# mod_B.net
KiCad netlist of a schematic drawn in EAGLE
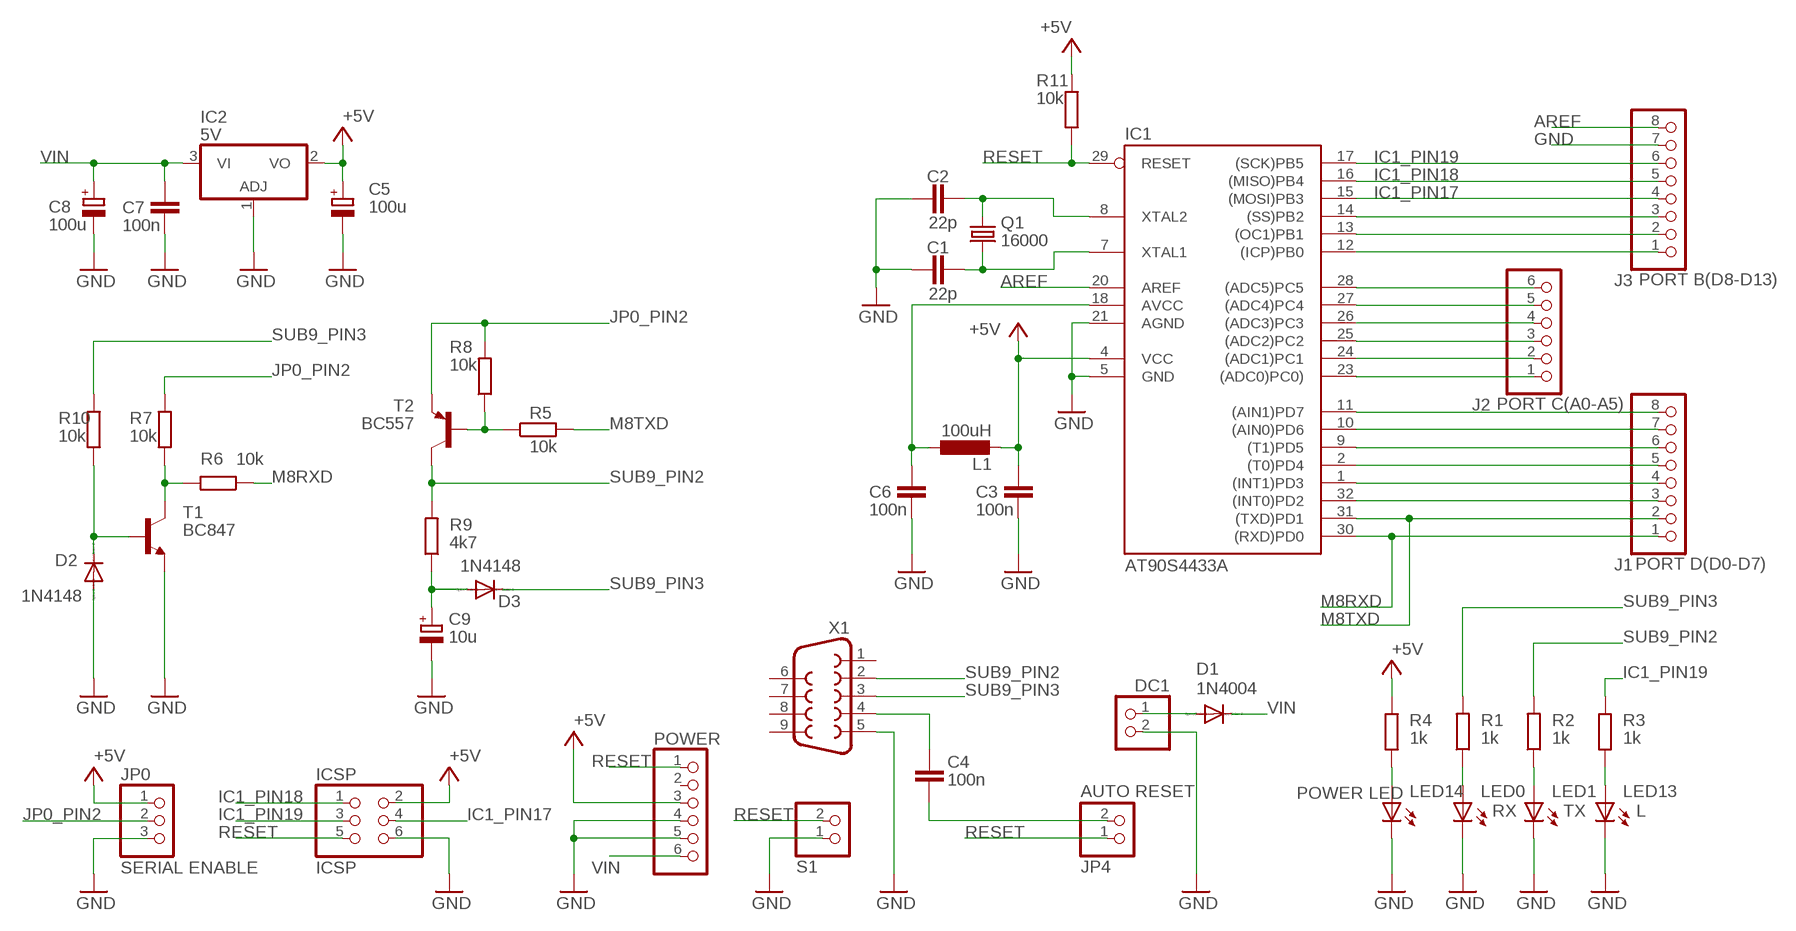
[diagram p0: schematic, sheet 1]

(export (version "E")
  (design (tool "Eeschema 10.0.6"))
  (components
    (comp (ref "C1")
      (value "22p")
      (footprint "eagle-import:C0805")
      (libsource (lib "eagle-import") (part "C-EUC0805"))
    )
    (comp (ref "C2")
      (value "22p")
      (footprint "eagle-import:C0805")
      (libsource (lib "eagle-import") (part "C-EUC0805"))
    )
    (comp (ref "C3")
      (value "100n")
      (footprint "eagle-import:C0805")
      (libsource (lib "eagle-import") (part "C-EUC0805"))
    )
    (comp (ref "C4")
      (value "100n")
      (footprint "eagle-import:C0805")
      (libsource (lib "eagle-import") (part "C-EUC0805"))
    )
    (comp (ref "C5")
      (value "100u")
      (footprint "eagle-import:PANASONIC_D")
      (libsource (lib "eagle-import") (part "CPOL-EUD"))
    )
    (comp (ref "C6")
      (value "100n")
      (footprint "eagle-import:C0805")
      (libsource (lib "eagle-import") (part "C-EUC0805"))
    )
    (comp (ref "C7")
      (value "100n")
      (footprint "eagle-import:C0805")
      (libsource (lib "eagle-import") (part "C-EUC0805"))
    )
    (comp (ref "C8")
      (value "100u")
      (footprint "eagle-import:PANASONIC_D")
      (libsource (lib "eagle-import") (part "CPOL-EUD"))
    )
    (comp (ref "C9")
      (value "10u")
      (footprint "eagle-import:PANASONIC_B")
      (libsource (lib "eagle-import") (part "CPOL-EUB"))
    )
    (comp (ref "D1")
      (value "1N4004")
      (footprint "eagle-import:SOD80C")
      (libsource (lib "eagle-import") (part "DIODE-SOD80C"))
    )
    (comp (ref "D2")
      (value "1N4148")
      (footprint "eagle-import:SOD80C")
      (libsource (lib "eagle-import") (part "DIODE-SOD80C"))
    )
    (comp (ref "D3")
      (value "1N4148")
      (footprint "eagle-import:SOD80C")
      (libsource (lib "eagle-import") (part "DIODE-SOD80C"))
    )
    (comp (ref "DC1")
      (value "PINHD-1X2")
      (footprint "eagle-import:1X02")
      (libsource (lib "eagle-import") (part "PINHD-1X2"))
    )
    (comp (ref "IC1")
      (value "AT90S4433A")
      (footprint "eagle-import:TQFP32-08")
      (libsource (lib "eagle-import") (part "AT90S4433A"))
    )
    (comp (ref "IC2")
      (value "5V")
      (footprint "eagle-import:SOT223")
      (libsource (lib "eagle-import") (part "AMS1117"))
    )
    (comp (ref "ICSP")
      (value "ICSP")
      (footprint "eagle-import:2X03")
      (libsource (lib "eagle-import") (part "PINHD-2X3"))
    )
    (comp (ref "J1")
      (value "PORT D(D0-D7)")
      (footprint "eagle-import:1X08")
      (libsource (lib "eagle-import") (part "PINHD-1X8"))
    )
    (comp (ref "J2")
      (value "PORT C(A0-A5)")
      (footprint "eagle-import:1X06")
      (libsource (lib "eagle-import") (part "PINHD-1X6"))
    )
    (comp (ref "J3")
      (value "PORT B(D8-D13)")
      (footprint "eagle-import:1X08")
      (libsource (lib "eagle-import") (part "PINHD-1X8"))
    )
    (comp (ref "JP0")
      (value "SERIAL ENABLE")
      (footprint "eagle-import:1X03")
      (libsource (lib "eagle-import") (part "PINHD-1X3"))
    )
    (comp (ref "JP4")
      (value "AUTO RESET")
      (footprint "eagle-import:1X02")
      (libsource (lib "eagle-import") (part "PINHD-1X2"))
    )
    (comp (ref "L1")
      (value "100uH")
      (footprint "eagle-import:L1812")
      (libsource (lib "eagle-import") (part "L-EUL1812"))
    )
    (comp (ref "LED0")
      (value "RX")
      (footprint "eagle-import:CHIP-LED0603")
      (libsource (lib "eagle-import") (part "LEDCHIP-LED0603"))
    )
    (comp (ref "LED1")
      (value "TX")
      (footprint "eagle-import:CHIP-LED0603")
      (libsource (lib "eagle-import") (part "LEDCHIP-LED0603"))
    )
    (comp (ref "LED13")
      (value "L")
      (footprint "eagle-import:CHIP-LED0603")
      (libsource (lib "eagle-import") (part "LEDCHIP-LED0603"))
    )
    (comp (ref "LED14")
      (value "POWER LED")
      (footprint "eagle-import:CHIP-LED0603")
      (libsource (lib "eagle-import") (part "LEDCHIP-LED0603"))
    )
    (comp (ref "POWER")
      (value "PINHD-1X6")
      (footprint "eagle-import:1X06")
      (libsource (lib "eagle-import") (part "PINHD-1X6"))
    )
    (comp (ref "Q1")
      (value "16000")
      (footprint "eagle-import:SM49")
      (libsource (lib "eagle-import") (part "CRYSTALSM49"))
    )
    (comp (ref "R1")
      (value "1k")
      (footprint "eagle-import:M0805")
      (libsource (lib "eagle-import") (part "R-EU_M0805"))
    )
    (comp (ref "R2")
      (value "1k")
      (footprint "eagle-import:M0805")
      (libsource (lib "eagle-import") (part "R-EU_M0805"))
    )
    (comp (ref "R3")
      (value "1k")
      (footprint "eagle-import:M0805")
      (libsource (lib "eagle-import") (part "R-EU_M0805"))
    )
    (comp (ref "R4")
      (value "1k")
      (footprint "eagle-import:M0805")
      (libsource (lib "eagle-import") (part "R-EU_M0805"))
    )
    (comp (ref "R5")
      (value "10k")
      (footprint "eagle-import:M0805")
      (libsource (lib "eagle-import") (part "R-EU_M0805"))
    )
    (comp (ref "R6")
      (value "10k")
      (footprint "eagle-import:M0805")
      (libsource (lib "eagle-import") (part "R-EU_M0805"))
    )
    (comp (ref "R7")
      (value "10k")
      (footprint "eagle-import:M0805")
      (libsource (lib "eagle-import") (part "R-EU_M0805"))
    )
    (comp (ref "R8")
      (value "10k")
      (footprint "eagle-import:M0805")
      (libsource (lib "eagle-import") (part "R-EU_M0805"))
    )
    (comp (ref "R9")
      (value "4k7")
      (footprint "eagle-import:R1206")
      (libsource (lib "eagle-import") (part "R-EU_R1206"))
    )
    (comp (ref "R10")
      (value "10k")
      (footprint "eagle-import:M0805")
      (libsource (lib "eagle-import") (part "R-EU_M0805"))
    )
    (comp (ref "R11")
      (value "10k")
      (footprint "eagle-import:M0805")
      (libsource (lib "eagle-import") (part "R-EU_M0805"))
    )
    (comp (ref "S1")
      (value "PINHD-1X2")
      (footprint "eagle-import:1X02")
      (libsource (lib "eagle-import") (part "PINHD-1X2"))
    )
    (comp (ref "T1")
      (value "BC847")
      (footprint "eagle-import:SOT23")
      (libsource (lib "eagle-import") (part "BC847"))
    )
    (comp (ref "T2")
      (value "BC557")
      (footprint "eagle-import:SOT23-BEC")
      (libsource (lib "eagle-import") (part "-PNP-SOT23-BECBC857A"))
    )
    (comp (ref "X1")
      (value "F09H")
      (footprint "eagle-import:F09H")
      (libsource (lib "eagle-import") (part "F09H"))
    )
  )
  (nets
    (net (code "1") (name "+5V") (class "Default")
      (node (ref "C3") (pin "1") (pinfunction "1_1") (pintype "passive"))
      (node (ref "C5") (pin "+") (pinfunction "+_+") (pintype "passive"))
      (node (ref "IC1") (pin "4") (pinfunction "VCC_4") (pintype "power_in"))
      (node (ref "IC2") (pin "2") (pinfunction "VO_2") (pintype "passive"))
      (node (ref "ICSP") (pin "2") (pinfunction "2_2") (pintype "passive"))
      (node (ref "JP0") (pin "1") (pinfunction "1_1") (pintype "passive"))
      (node (ref "L1") (pin "2") (pinfunction "2_2") (pintype "passive"))
      (node (ref "POWER") (pin "3") (pinfunction "3_3") (pintype "passive"))
      (node (ref "R11") (pin "2") (pinfunction "2_2") (pintype "passive"))
      (node (ref "R4") (pin "1") (pinfunction "1_1") (pintype "passive"))
    )
    (net (code "2") (name "/AREF") (class "Default")
      (node (ref "IC1") (pin "20") (pinfunction "AREF_20") (pintype "passive"))
      (node (ref "J3") (pin "8") (pinfunction "8_8") (pintype "passive"))
    )
    (net (code "3") (name "/IC1_PIN17") (class "Default")
      (node (ref "IC1") (pin "15") (pinfunction "(MOSI)PB3_15") (pintype "bidirectional"))
      (node (ref "ICSP") (pin "4") (pinfunction "4_4") (pintype "passive"))
      (node (ref "J3") (pin "4") (pinfunction "4_4") (pintype "passive"))
    )
    (net (code "4") (name "/IC1_PIN18") (class "Default")
      (node (ref "IC1") (pin "16") (pinfunction "(MISO)PB4_16") (pintype "bidirectional"))
      (node (ref "ICSP") (pin "1") (pinfunction "1_1") (pintype "passive"))
      (node (ref "J3") (pin "5") (pinfunction "5_5") (pintype "passive"))
    )
    (net (code "5") (name "/IC1_PIN19") (class "Default")
      (node (ref "IC1") (pin "17") (pinfunction "(SCK)PB5_17") (pintype "bidirectional"))
      (node (ref "ICSP") (pin "3") (pinfunction "3_3") (pintype "passive"))
      (node (ref "J3") (pin "6") (pinfunction "6_6") (pintype "passive"))
      (node (ref "R3") (pin "1") (pinfunction "1_1") (pintype "passive"))
    )
    (net (code "6") (name "/JP0_PIN2") (class "Default")
      (node (ref "JP0") (pin "2") (pinfunction "2_2") (pintype "passive"))
      (node (ref "R7") (pin "2") (pinfunction "2_2") (pintype "passive"))
      (node (ref "R8") (pin "2") (pinfunction "2_2") (pintype "passive"))
      (node (ref "T2") (pin "E") (pinfunction "E_E") (pintype "passive"))
    )
    (net (code "7") (name "/M8RXD") (class "Default")
      (node (ref "IC1") (pin "30") (pinfunction "(RXD)PD0_30") (pintype "bidirectional"))
      (node (ref "J1") (pin "1") (pinfunction "1_1") (pintype "passive"))
      (node (ref "R6") (pin "1") (pinfunction "1_1") (pintype "passive"))
    )
    (net (code "8") (name "/M8TXD") (class "Default")
      (node (ref "IC1") (pin "31") (pinfunction "(TXD)PD1_31") (pintype "bidirectional"))
      (node (ref "J1") (pin "2") (pinfunction "2_2") (pintype "passive"))
      (node (ref "R5") (pin "2") (pinfunction "2_2") (pintype "passive"))
    )
    (net (code "9") (name "/RESET") (class "Default")
      (node (ref "IC1") (pin "29") (pinfunction "RESET_29") (pintype "input"))
      (node (ref "ICSP") (pin "5") (pinfunction "5_5") (pintype "passive"))
      (node (ref "JP4") (pin "1") (pinfunction "1_1") (pintype "passive"))
      (node (ref "POWER") (pin "1") (pinfunction "1_1") (pintype "passive"))
      (node (ref "R11") (pin "1") (pinfunction "1_1") (pintype "passive"))
      (node (ref "S1") (pin "2") (pinfunction "2_2") (pintype "passive"))
    )
    (net (code "10") (name "/SUB9_PIN2") (class "Default")
      (node (ref "R2") (pin "2") (pinfunction "2_2") (pintype "passive"))
      (node (ref "R9") (pin "2") (pinfunction "2_2") (pintype "passive"))
      (node (ref "T2") (pin "C") (pinfunction "C_C") (pintype "passive"))
      (node (ref "X1") (pin "2") (pinfunction "2_2") (pintype "passive"))
    )
    (net (code "11") (name "/SUB9_PIN3") (class "Default")
      (node (ref "D3") (pin "C") (pinfunction "C_C") (pintype "passive"))
      (node (ref "R1") (pin "2") (pinfunction "2_2") (pintype "passive"))
      (node (ref "R10") (pin "2") (pinfunction "2_2") (pintype "passive"))
      (node (ref "X1") (pin "3") (pinfunction "3_3") (pintype "passive"))
    )
    (net (code "12") (name "/VIN") (class "Default")
      (node (ref "C7") (pin "1") (pinfunction "1_1") (pintype "passive"))
      (node (ref "C8") (pin "+") (pinfunction "+_+") (pintype "passive"))
      (node (ref "D1") (pin "C") (pinfunction "C_C") (pintype "passive"))
      (node (ref "IC2") (pin "3") (pinfunction "VI_3") (pintype "input"))
      (node (ref "POWER") (pin "6") (pinfunction "6_6") (pintype "passive"))
    )
    (net (code "13") (name "GND") (class "Default")
      (node (ref "C1") (pin "1") (pinfunction "1_1") (pintype "passive"))
      (node (ref "C2") (pin "1") (pinfunction "1_1") (pintype "passive"))
      (node (ref "C3") (pin "2") (pinfunction "2_2") (pintype "passive"))
      (node (ref "C5") (pin "-") (pinfunction "-_-") (pintype "passive"))
      (node (ref "C6") (pin "2") (pinfunction "2_2") (pintype "passive"))
      (node (ref "C7") (pin "2") (pinfunction "2_2") (pintype "passive"))
      (node (ref "C8") (pin "-") (pinfunction "-_-") (pintype "passive"))
      (node (ref "C9") (pin "-") (pinfunction "-_-") (pintype "passive"))
      (node (ref "D2") (pin "A") (pinfunction "A_A") (pintype "passive"))
      (node (ref "DC1") (pin "2") (pinfunction "2_2") (pintype "passive"))
      (node (ref "IC1") (pin "21") (pinfunction "AGND_21") (pintype "power_in"))
      (node (ref "IC1") (pin "5") (pinfunction "GND_5") (pintype "power_in"))
      (node (ref "IC2") (pin "1") (pinfunction "ADJ_1") (pintype "input"))
      (node (ref "ICSP") (pin "6") (pinfunction "6_6") (pintype "passive"))
      (node (ref "J3") (pin "7") (pinfunction "7_7") (pintype "passive"))
      (node (ref "JP0") (pin "3") (pinfunction "3_3") (pintype "passive"))
      (node (ref "LED0") (pin "C") (pinfunction "C_C") (pintype "passive"))
      (node (ref "LED1") (pin "C") (pinfunction "C_C") (pintype "passive"))
      (node (ref "LED13") (pin "C") (pinfunction "C_C") (pintype "passive"))
      (node (ref "LED14") (pin "C") (pinfunction "C_C") (pintype "passive"))
      (node (ref "POWER") (pin "4") (pinfunction "4_4") (pintype "passive"))
      (node (ref "POWER") (pin "5") (pinfunction "5_5") (pintype "passive"))
      (node (ref "S1") (pin "1") (pinfunction "1_1") (pintype "passive"))
      (node (ref "T1") (pin "2") (pinfunction "E_2") (pintype "passive"))
      (node (ref "X1") (pin "5") (pinfunction "5_5") (pintype "passive"))
    )
    (net (code "14") (name "Net-(C4-Pad1)") (class "Default")
      (node (ref "C4") (pin "1") (pinfunction "1_1") (pintype "passive"))
      (node (ref "X1") (pin "4") (pinfunction "4_4") (pintype "passive"))
    )
    (net (code "15") (name "Net-(C4-Pad2)") (class "Default")
      (node (ref "C4") (pin "2") (pinfunction "2_2") (pintype "passive"))
      (node (ref "JP4") (pin "2") (pinfunction "2_2") (pintype "passive"))
    )
    (net (code "16") (name "Net-(C9-Pad+)") (class "Default")
      (node (ref "C9") (pin "+") (pinfunction "+_+") (pintype "passive"))
      (node (ref "D3") (pin "A") (pinfunction "A_A") (pintype "passive"))
      (node (ref "R9") (pin "1") (pinfunction "1_1") (pintype "passive"))
    )
    (net (code "17") (name "Net-(D1-PadA)") (class "Default")
      (node (ref "D1") (pin "A") (pinfunction "A_A") (pintype "passive"))
      (node (ref "DC1") (pin "1") (pinfunction "1_1") (pintype "passive"))
    )
    (net (code "18") (name "Net-(IC1-(ADC0)PC0))") (class "Default")
      (node (ref "IC1") (pin "23") (pinfunction "(ADC0)PC0)_23") (pintype "bidirectional"))
      (node (ref "J2") (pin "1") (pinfunction "1_1") (pintype "passive"))
    )
    (net (code "19") (name "Net-(IC1-(ADC1)PC1)") (class "Default")
      (node (ref "IC1") (pin "24") (pinfunction "(ADC1)PC1_24") (pintype "bidirectional"))
      (node (ref "J2") (pin "2") (pinfunction "2_2") (pintype "passive"))
    )
    (net (code "20") (name "Net-(IC1-(ADC2)PC2)") (class "Default")
      (node (ref "IC1") (pin "25") (pinfunction "(ADC2)PC2_25") (pintype "bidirectional"))
      (node (ref "J2") (pin "3") (pinfunction "3_3") (pintype "passive"))
    )
    (net (code "21") (name "Net-(IC1-(ADC3)PC3)") (class "Default")
      (node (ref "IC1") (pin "26") (pinfunction "(ADC3)PC3_26") (pintype "bidirectional"))
      (node (ref "J2") (pin "4") (pinfunction "4_4") (pintype "passive"))
    )
    (net (code "22") (name "Net-(IC1-(ADC4)PC4)") (class "Default")
      (node (ref "IC1") (pin "27") (pinfunction "(ADC4)PC4_27") (pintype "bidirectional"))
      (node (ref "J2") (pin "5") (pinfunction "5_5") (pintype "passive"))
    )
    (net (code "23") (name "Net-(IC1-(ADC5)PC5)") (class "Default")
      (node (ref "IC1") (pin "28") (pinfunction "(ADC5)PC5_28") (pintype "bidirectional"))
      (node (ref "J2") (pin "6") (pinfunction "6_6") (pintype "passive"))
    )
    (net (code "24") (name "Net-(IC1-(AIN0)PD6)") (class "Default")
      (node (ref "IC1") (pin "10") (pinfunction "(AIN0)PD6_10") (pintype "bidirectional"))
      (node (ref "J1") (pin "7") (pinfunction "7_7") (pintype "passive"))
    )
    (net (code "25") (name "Net-(IC1-(AIN1)PD7)") (class "Default")
      (node (ref "IC1") (pin "11") (pinfunction "(AIN1)PD7_11") (pintype "bidirectional"))
      (node (ref "J1") (pin "8") (pinfunction "8_8") (pintype "passive"))
    )
    (net (code "26") (name "Net-(IC1-(ICP)PB0)") (class "Default")
      (node (ref "IC1") (pin "12") (pinfunction "(ICP)PB0_12") (pintype "bidirectional"))
      (node (ref "J3") (pin "1") (pinfunction "1_1") (pintype "passive"))
    )
    (net (code "27") (name "Net-(IC1-(INT0)PD2)") (class "Default")
      (node (ref "IC1") (pin "32") (pinfunction "(INT0)PD2_32") (pintype "bidirectional"))
      (node (ref "J1") (pin "3") (pinfunction "3_3") (pintype "passive"))
    )
    (net (code "28") (name "Net-(IC1-(INT1)PD3)") (class "Default")
      (node (ref "IC1") (pin "1") (pinfunction "(INT1)PD3_1") (pintype "bidirectional"))
      (node (ref "J1") (pin "4") (pinfunction "4_4") (pintype "passive"))
    )
    (net (code "29") (name "Net-(IC1-(OC1)PB1)") (class "Default")
      (node (ref "IC1") (pin "13") (pinfunction "(OC1)PB1_13") (pintype "bidirectional"))
      (node (ref "J3") (pin "2") (pinfunction "2_2") (pintype "passive"))
    )
    (net (code "30") (name "Net-(IC1-(SS)PB2)") (class "Default")
      (node (ref "IC1") (pin "14") (pinfunction "(SS)PB2_14") (pintype "bidirectional"))
      (node (ref "J3") (pin "3") (pinfunction "3_3") (pintype "passive"))
    )
    (net (code "31") (name "Net-(IC1-(T0)PD4)") (class "Default")
      (node (ref "IC1") (pin "2") (pinfunction "(T0)PD4_2") (pintype "bidirectional"))
      (node (ref "J1") (pin "5") (pinfunction "5_5") (pintype "passive"))
    )
    (net (code "32") (name "Net-(IC1-(T1)PD5)") (class "Default")
      (node (ref "IC1") (pin "9") (pinfunction "(T1)PD5_9") (pintype "bidirectional"))
      (node (ref "J1") (pin "6") (pinfunction "6_6") (pintype "passive"))
    )
    (net (code "33") (name "Net-(IC1-AVCC)") (class "Default")
      (node (ref "C6") (pin "1") (pinfunction "1_1") (pintype "passive"))
      (node (ref "IC1") (pin "18") (pinfunction "AVCC_18") (pintype "power_in"))
      (node (ref "L1") (pin "1") (pinfunction "1_1") (pintype "passive"))
    )
    (net (code "34") (name "Net-(IC1-XTAL1)") (class "Default")
      (node (ref "C1") (pin "2") (pinfunction "2_2") (pintype "passive"))
      (node (ref "IC1") (pin "7") (pinfunction "XTAL1_7") (pintype "bidirectional"))
      (node (ref "Q1") (pin "1") (pinfunction "1_1") (pintype "passive"))
    )
    (net (code "35") (name "Net-(IC1-XTAL2)") (class "Default")
      (node (ref "C2") (pin "2") (pinfunction "2_2") (pintype "passive"))
      (node (ref "IC1") (pin "8") (pinfunction "XTAL2_8") (pintype "bidirectional"))
      (node (ref "Q1") (pin "2") (pinfunction "2_2") (pintype "passive"))
    )
    (net (code "36") (name "Net-(LED0-PadA)") (class "Default")
      (node (ref "LED0") (pin "A") (pinfunction "A_A") (pintype "passive"))
      (node (ref "R1") (pin "1") (pinfunction "1_1") (pintype "passive"))
    )
    (net (code "37") (name "Net-(LED1-PadA)") (class "Default")
      (node (ref "LED1") (pin "A") (pinfunction "A_A") (pintype "passive"))
      (node (ref "R2") (pin "1") (pinfunction "1_1") (pintype "passive"))
    )
    (net (code "38") (name "Net-(LED13-PadA)") (class "Default")
      (node (ref "LED13") (pin "A") (pinfunction "A_A") (pintype "passive"))
      (node (ref "R3") (pin "2") (pinfunction "2_2") (pintype "passive"))
    )
    (net (code "39") (name "Net-(LED14-PadA)") (class "Default")
      (node (ref "LED14") (pin "A") (pinfunction "A_A") (pintype "passive"))
      (node (ref "R4") (pin "2") (pinfunction "2_2") (pintype "passive"))
    )
    (net (code "40") (name "Net-(R5-Pad1)") (class "Default")
      (node (ref "R5") (pin "1") (pinfunction "1_1") (pintype "passive"))
      (node (ref "R8") (pin "1") (pinfunction "1_1") (pintype "passive"))
      (node (ref "T2") (pin "B") (pinfunction "B_B") (pintype "passive"))
    )
    (net (code "41") (name "Net-(T1-B)") (class "Default")
      (node (ref "D2") (pin "C") (pinfunction "C_C") (pintype "passive"))
      (node (ref "R10") (pin "1") (pinfunction "1_1") (pintype "passive"))
      (node (ref "T1") (pin "1") (pinfunction "B_1") (pintype "passive"))
    )
    (net (code "42") (name "Net-(T1-C)") (class "Default")
      (node (ref "R6") (pin "2") (pinfunction "2_2") (pintype "passive"))
      (node (ref "R7") (pin "1") (pinfunction "1_1") (pintype "passive"))
      (node (ref "T1") (pin "3") (pinfunction "C_3") (pintype "passive"))
    )
    (net (code "43") (name "unconnected-(POWER-Pad2)") (class "Default")
      (node (ref "POWER") (pin "2") (pinfunction "2_2") (pintype "passive"))
    )
    (net (code "44") (name "unconnected-(X1-Pad1)") (class "Default")
      (node (ref "X1") (pin "1") (pinfunction "1_1") (pintype "passive"))
    )
    (net (code "45") (name "unconnected-(X1-Pad6)") (class "Default")
      (node (ref "X1") (pin "6") (pinfunction "6_6") (pintype "passive"))
    )
    (net (code "46") (name "unconnected-(X1-Pad7)") (class "Default")
      (node (ref "X1") (pin "7") (pinfunction "7_7") (pintype "passive"))
    )
    (net (code "47") (name "unconnected-(X1-Pad8)") (class "Default")
      (node (ref "X1") (pin "8") (pinfunction "8_8") (pintype "passive"))
    )
    (net (code "48") (name "unconnected-(X1-Pad9)") (class "Default")
      (node (ref "X1") (pin "9") (pinfunction "9_9") (pintype "passive"))
    )
  )
)
